# STM32lab.net
KiCad netlist of a schematic drawn in Altium Designer
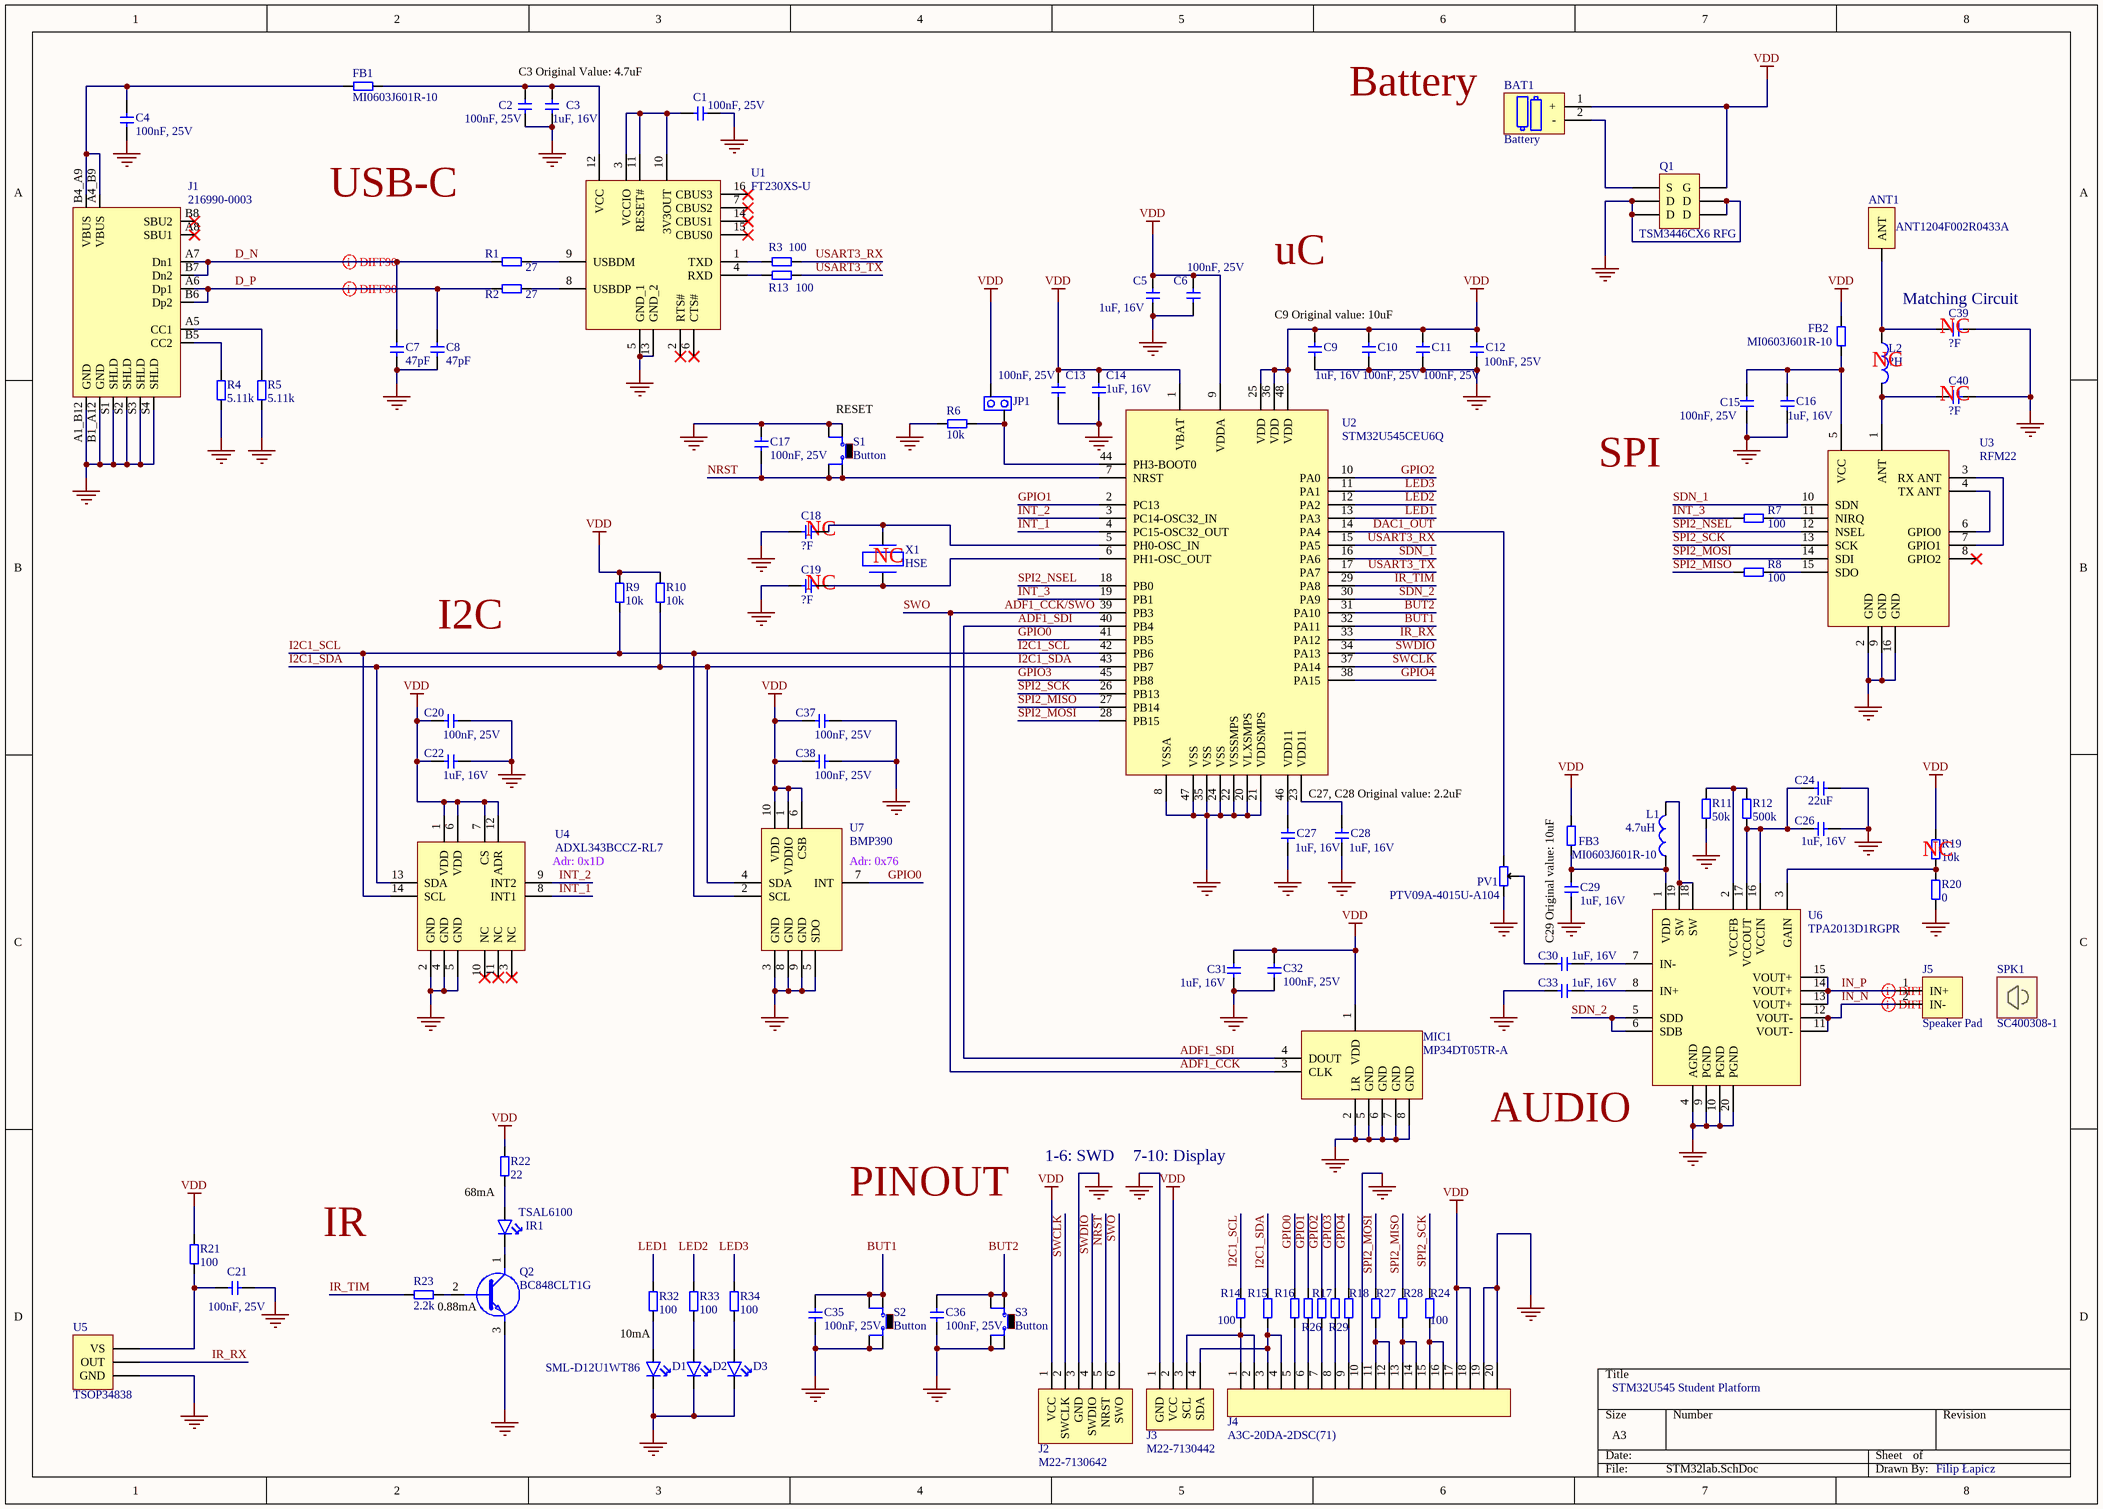
[diagram p0: STM32lab.SchDoc]

(export (version "E")
  (design (tool "Eeschema 10.0.6"))
  (components
    (comp (ref "ANT1")
      (value "ANT1204F002R0433A")
      (footprint "CHIP_R0433A_YAG")
      (description "Antennas 433MHz 50 Ohm 1W CHIP ANTENNA")
      (fields (field (name "MANUFACTURER") "Pulse"))
      (libsource (lib "Schlib") (part "ANT1204F002R0433A"))
    )
    (comp (ref "BAT1") (value "Battery") (footprint "2462") (libsource (lib "Schlib") (part "Battery")))
    (comp (ref "C1")
      (value "100nF, 25V")
      (footprint "CAPC1608X90N")
      (description "Multilayer Ceramic Capacitors MLCC - SMD/SMT 25V 0.1uF X5R 0603 10 %")
      (fields
        (field (name "MANUFACTURER") "Samsung")
        (field (name "MANUFACTURER PART NUMBER") "CL10B104JB8NNND")
      )
      (libsource (lib "Schlib") (part "TMK107BJ104KA-T"))
    )
    (comp (ref "C2")
      (value "100nF, 25V")
      (footprint "CAPC1608X90N")
      (description "Multilayer Ceramic Capacitors MLCC - SMD/SMT 25V 0.1uF X5R 0603 10 %")
      (fields
        (field (name "MANUFACTURER") "Samsung")
        (field (name "MANUFACTURER PART NUMBER") "CL10B104JB8NNND")
      )
      (libsource (lib "Schlib") (part "TMK107BJ104KA-T"))
    )
    (comp (ref "C3")
      (value "1uF, 16V")
      (footprint "CAPC1608X90N")
      (description "Multilayer Ceramic Capacitors (High dielectric type), 16V, 1 uF, ± 20 %, 0603, X5R, RoHS")
      (fields
        (field (name "MANUFACTURER") "Taiyo Yuden")
        (field (name "MANUFACTURER PART NUMBER") "EMK107BJ105MA-T")
      )
      (libsource (lib "Schlib") (part "EMK107BJ105MA-T"))
    )
    (comp (ref "C4")
      (value "100nF, 25V")
      (footprint "CAPC1608X90N")
      (description "Multilayer Ceramic Capacitors MLCC - SMD/SMT 25V 0.1uF X5R 0603 10 %")
      (fields
        (field (name "MANUFACTURER") "Samsung")
        (field (name "MANUFACTURER PART NUMBER") "CL10B104JB8NNND")
      )
      (libsource (lib "Schlib") (part "TMK107BJ104KA-T"))
    )
    (comp (ref "C5")
      (value "1uF, 16V")
      (footprint "CAPC1608X90N")
      (description "Multilayer Ceramic Capacitors (High dielectric type), 16V, 1 uF, ± 20 %, 0603, X5R, RoHS")
      (fields
        (field (name "MANUFACTURER") "Taiyo Yuden")
        (field (name "MANUFACTURER PART NUMBER") "EMK107BJ105MA-T")
      )
      (libsource (lib "Schlib") (part "EMK107BJ105MA-T"))
    )
    (comp (ref "C6")
      (value "100nF, 25V")
      (footprint "CAPC1608X90N")
      (description "Multilayer Ceramic Capacitors MLCC - SMD/SMT 25V 0.1uF X5R 0603 10 %")
      (fields
        (field (name "MANUFACTURER") "Samsung")
        (field (name "MANUFACTURER PART NUMBER") "CL10B104JB8NNND")
      )
      (libsource (lib "Schlib") (part "TMK107BJ104KA-T"))
    )
    (comp (ref "C7")
      (value "47pF")
      (footprint "CAPC1608X90N")
      (description "No model capacitor")
      (libsource (lib "Schlib") (part "Capacitor"))
    )
    (comp (ref "C8")
      (value "47pF")
      (footprint "CAPC1608X90N")
      (description "No model capacitor")
      (libsource (lib "Schlib") (part "Capacitor"))
    )
    (comp (ref "C9")
      (value "1uF, 16V")
      (footprint "CAPC1608X90N")
      (description "Multilayer Ceramic Capacitors (High dielectric type), 16V, 1 uF, ± 20 %, 0603, X5R, RoHS")
      (fields
        (field (name "MANUFACTURER") "Taiyo Yuden")
        (field (name "MANUFACTURER PART NUMBER") "EMK107BJ105MA-T")
      )
      (libsource (lib "Schlib") (part "EMK107BJ105MA-T"))
    )
    (comp (ref "C10")
      (value "100nF, 25V")
      (footprint "CAPC1608X90N")
      (description "Multilayer Ceramic Capacitors MLCC - SMD/SMT 25V 0.1uF X5R 0603 10 %")
      (fields
        (field (name "MANUFACTURER") "Samsung")
        (field (name "MANUFACTURER PART NUMBER") "CL10B104JB8NNND")
      )
      (libsource (lib "Schlib") (part "TMK107BJ104KA-T"))
    )
    (comp (ref "C11")
      (value "100nF, 25V")
      (footprint "CAPC1608X90N")
      (description "Multilayer Ceramic Capacitors MLCC - SMD/SMT 25V 0.1uF X5R 0603 10 %")
      (fields
        (field (name "MANUFACTURER") "Samsung")
        (field (name "MANUFACTURER PART NUMBER") "CL10B104JB8NNND")
      )
      (libsource (lib "Schlib") (part "TMK107BJ104KA-T"))
    )
    (comp (ref "C12")
      (value "100nF, 25V")
      (footprint "CAPC1608X90N")
      (description "Multilayer Ceramic Capacitors MLCC - SMD/SMT 25V 0.1uF X5R 0603 10 %")
      (fields
        (field (name "MANUFACTURER") "Samsung")
        (field (name "MANUFACTURER PART NUMBER") "CL10B104JB8NNND")
      )
      (libsource (lib "Schlib") (part "TMK107BJ104KA-T"))
    )
    (comp (ref "C13")
      (value "100nF, 25V")
      (footprint "CAPC1608X90N")
      (description "Multilayer Ceramic Capacitors MLCC - SMD/SMT 25V 0.1uF X5R 0603 10 %")
      (fields
        (field (name "MANUFACTURER") "Samsung")
        (field (name "MANUFACTURER PART NUMBER") "CL10B104JB8NNND")
      )
      (libsource (lib "Schlib") (part "TMK107BJ104KA-T"))
    )
    (comp (ref "C14")
      (value "1uF, 16V")
      (footprint "CAPC1608X90N")
      (description "Multilayer Ceramic Capacitors (High dielectric type), 16V, 1 uF, ± 20 %, 0603, X5R, RoHS")
      (fields
        (field (name "MANUFACTURER") "Taiyo Yuden")
        (field (name "MANUFACTURER PART NUMBER") "EMK107BJ105MA-T")
      )
      (libsource (lib "Schlib") (part "EMK107BJ105MA-T"))
    )
    (comp (ref "C15")
      (value "100nF, 25V")
      (footprint "CAPC1608X90N")
      (description "Multilayer Ceramic Capacitors MLCC - SMD/SMT 25V 0.1uF X5R 0603 10 %")
      (fields
        (field (name "MANUFACTURER") "Samsung")
        (field (name "MANUFACTURER PART NUMBER") "CL10B104JB8NNND")
      )
      (libsource (lib "Schlib") (part "TMK107BJ104KA-T"))
    )
    (comp (ref "C16")
      (value "1uF, 16V")
      (footprint "CAPC1608X90N")
      (description "Multilayer Ceramic Capacitors (High dielectric type), 16V, 1 uF, ± 20 %, 0603, X5R, RoHS")
      (fields
        (field (name "MANUFACTURER") "Taiyo Yuden")
        (field (name "MANUFACTURER PART NUMBER") "EMK107BJ105MA-T")
      )
      (libsource (lib "Schlib") (part "EMK107BJ105MA-T"))
    )
    (comp (ref "C17")
      (value "100nF, 25V")
      (footprint "CAPC1608X90N")
      (description "Multilayer Ceramic Capacitors MLCC - SMD/SMT 25V 0.1uF X5R 0603 10 %")
      (fields
        (field (name "MANUFACTURER") "Samsung")
        (field (name "MANUFACTURER PART NUMBER") "CL10B104JB8NNND")
      )
      (libsource (lib "Schlib") (part "TMK107BJ104KA-T"))
    )
    (comp (ref "C18")
      (value "?F")
      (footprint "CAPC1608X90N")
      (description "No model capacitor")
      (libsource (lib "Schlib") (part "Capacitor"))
    )
    (comp (ref "C19")
      (value "?F")
      (footprint "CAPC1608X90N")
      (description "No model capacitor")
      (libsource (lib "Schlib") (part "Capacitor"))
    )
    (comp (ref "C20")
      (value "100nF, 25V")
      (footprint "CAPC1608X90N")
      (description "Multilayer Ceramic Capacitors MLCC - SMD/SMT 25V 0.1uF X5R 0603 10 %")
      (fields
        (field (name "MANUFACTURER") "Samsung")
        (field (name "MANUFACTURER PART NUMBER") "CL10B104JB8NNND")
      )
      (libsource (lib "Schlib") (part "TMK107BJ104KA-T"))
    )
    (comp (ref "C21")
      (value "100nF, 25V")
      (footprint "CAPC1608X90N")
      (description "Multilayer Ceramic Capacitors MLCC - SMD/SMT 25V 0.1uF X5R 0603 10 %")
      (fields
        (field (name "MANUFACTURER") "Samsung")
        (field (name "MANUFACTURER PART NUMBER") "CL10B104JB8NNND")
      )
      (libsource (lib "Schlib") (part "TMK107BJ104KA-T"))
    )
    (comp (ref "C22")
      (value "1uF, 16V")
      (footprint "CAPC1608X90N")
      (description "Multilayer Ceramic Capacitors (High dielectric type), 16V, 1 uF, ± 20 %, 0603, X5R, RoHS")
      (fields
        (field (name "MANUFACTURER") "Taiyo Yuden")
        (field (name "MANUFACTURER PART NUMBER") "EMK107BJ105MA-T")
      )
      (libsource (lib "Schlib") (part "EMK107BJ105MA-T"))
    )
    (comp (ref "C24")
      (value "22uF")
      (footprint "CAPC1608X90N")
      (description "No model capacitor")
      (libsource (lib "Schlib") (part "Capacitor"))
    )
    (comp (ref "C26")
      (value "1uF, 16V")
      (footprint "CAPC1608X90N")
      (description "Multilayer Ceramic Capacitors (High dielectric type), 16V, 1 uF, ± 20 %, 0603, X5R, RoHS")
      (fields
        (field (name "MANUFACTURER") "Taiyo Yuden")
        (field (name "MANUFACTURER PART NUMBER") "EMK107BJ105MA-T")
      )
      (libsource (lib "Schlib") (part "EMK107BJ105MA-T"))
    )
    (comp (ref "C27")
      (value "1uF, 16V")
      (footprint "CAPC1608X90N")
      (description "Multilayer Ceramic Capacitors (High dielectric type), 16V, 1 uF, ± 20 %, 0603, X5R, RoHS")
      (fields
        (field (name "MANUFACTURER") "Taiyo Yuden")
        (field (name "MANUFACTURER PART NUMBER") "EMK107BJ105MA-T")
      )
      (libsource (lib "Schlib") (part "EMK107BJ105MA-T"))
    )
    (comp (ref "C28")
      (value "1uF, 16V")
      (footprint "CAPC1608X90N")
      (description "Multilayer Ceramic Capacitors (High dielectric type), 16V, 1 uF, ± 20 %, 0603, X5R, RoHS")
      (fields
        (field (name "MANUFACTURER") "Taiyo Yuden")
        (field (name "MANUFACTURER PART NUMBER") "EMK107BJ105MA-T")
      )
      (libsource (lib "Schlib") (part "EMK107BJ105MA-T"))
    )
    (comp (ref "C29")
      (value "1uF, 16V")
      (footprint "CAPC1608X90N")
      (description "Multilayer Ceramic Capacitors (High dielectric type), 16V, 1 uF, ± 20 %, 0603, X5R, RoHS")
      (fields
        (field (name "MANUFACTURER") "Taiyo Yuden")
        (field (name "MANUFACTURER PART NUMBER") "EMK107BJ105MA-T")
      )
      (libsource (lib "Schlib") (part "EMK107BJ105MA-T"))
    )
    (comp (ref "C30")
      (value "1uF, 16V")
      (footprint "CAPC1608X90N")
      (description "Multilayer Ceramic Capacitors (High dielectric type), 16V, 1 uF, ± 20 %, 0603, X5R, RoHS")
      (fields
        (field (name "MANUFACTURER") "Taiyo Yuden")
        (field (name "MANUFACTURER PART NUMBER") "EMK107BJ105MA-T")
      )
      (libsource (lib "Schlib") (part "EMK107BJ105MA-T"))
    )
    (comp (ref "C31")
      (value "1uF, 16V")
      (footprint "CAPC1608X90N")
      (description "Multilayer Ceramic Capacitors (High dielectric type), 16V, 1 uF, ± 20 %, 0603, X5R, RoHS")
      (fields
        (field (name "MANUFACTURER") "Taiyo Yuden")
        (field (name "MANUFACTURER PART NUMBER") "EMK107BJ105MA-T")
      )
      (libsource (lib "Schlib") (part "EMK107BJ105MA-T"))
    )
    (comp (ref "C32")
      (value "100nF, 25V")
      (footprint "CAPC1608X90N")
      (description "Multilayer Ceramic Capacitors MLCC - SMD/SMT 25V 0.1uF X5R 0603 10 %")
      (fields
        (field (name "MANUFACTURER") "Samsung")
        (field (name "MANUFACTURER PART NUMBER") "CL10B104JB8NNND")
      )
      (libsource (lib "Schlib") (part "TMK107BJ104KA-T"))
    )
    (comp (ref "C33")
      (value "1uF, 16V")
      (footprint "CAPC1608X90N")
      (description "Multilayer Ceramic Capacitors (High dielectric type), 16V, 1 uF, ± 20 %, 0603, X5R, RoHS")
      (fields
        (field (name "MANUFACTURER") "Taiyo Yuden")
        (field (name "MANUFACTURER PART NUMBER") "EMK107BJ105MA-T")
      )
      (libsource (lib "Schlib") (part "EMK107BJ105MA-T"))
    )
    (comp (ref "C35")
      (value "100nF, 25V")
      (footprint "CAPC1608X90N")
      (description "Multilayer Ceramic Capacitors MLCC - SMD/SMT 25V 0.1uF X5R 0603 10 %")
      (fields
        (field (name "MANUFACTURER") "Samsung")
        (field (name "MANUFACTURER PART NUMBER") "CL10B104JB8NNND")
      )
      (libsource (lib "Schlib") (part "TMK107BJ104KA-T"))
    )
    (comp (ref "C36")
      (value "100nF, 25V")
      (footprint "CAPC1608X90N")
      (description "Multilayer Ceramic Capacitors MLCC - SMD/SMT 25V 0.1uF X5R 0603 10 %")
      (fields
        (field (name "MANUFACTURER") "Samsung")
        (field (name "MANUFACTURER PART NUMBER") "CL10B104JB8NNND")
      )
      (libsource (lib "Schlib") (part "TMK107BJ104KA-T"))
    )
    (comp (ref "C37")
      (value "100nF, 25V")
      (footprint "CAPC1608X90N")
      (description "Multilayer Ceramic Capacitors MLCC - SMD/SMT 25V 0.1uF X5R 0603 10 %")
      (fields
        (field (name "MANUFACTURER") "Samsung")
        (field (name "MANUFACTURER PART NUMBER") "CL10B104JB8NNND")
      )
      (libsource (lib "Schlib") (part "TMK107BJ104KA-T"))
    )
    (comp (ref "C38")
      (value "100nF, 25V")
      (footprint "CAPC1608X90N")
      (description "Multilayer Ceramic Capacitors MLCC - SMD/SMT 25V 0.1uF X5R 0603 10 %")
      (fields
        (field (name "MANUFACTURER") "Samsung")
        (field (name "MANUFACTURER PART NUMBER") "CL10B104JB8NNND")
      )
      (libsource (lib "Schlib") (part "TMK107BJ104KA-T"))
    )
    (comp (ref "C39")
      (value "?F")
      (footprint "CAPC1608X90N")
      (description "No model capacitor")
      (libsource (lib "Schlib") (part "Capacitor"))
    )
    (comp (ref "C40")
      (value "?F")
      (footprint "CAPC1608X90N")
      (description "No model capacitor")
      (libsource (lib "Schlib") (part "Capacitor"))
    )
    (comp (ref "D1")
      (value "SML-D12U1WT86")
      (footprint "LEDC1608X65N")
      (description "Single Color LED, Red, Milky White, 1.2mm")
      (fields (field (name "MANUFACTURER") "Rohm"))
      (libsource (lib "Schlib") (part "SML-D12U1WT86"))
    )
    (comp (ref "D2")
      (value "SML-D12U1WT86")
      (footprint "LEDC1608X65N")
      (description "Single Color LED, Red, Milky White, 1.2mm")
      (fields (field (name "MANUFACTURER") "Rohm"))
      (libsource (lib "Schlib") (part "SML-D12U1WT86"))
    )
    (comp (ref "D3")
      (value "SML-D12U1WT86")
      (footprint "LEDC1608X65N")
      (description "Single Color LED, Red, Milky White, 1.2mm")
      (fields (field (name "MANUFACTURER") "Rohm"))
      (libsource (lib "Schlib") (part "SML-D12U1WT86"))
    )
    (comp (ref "FB1")
      (value "MI0603J601R-10")
      (footprint "RESC1608X55N")
      (description "Ferrite Chip, 1 Function(s), 1A, 2 Pin(s)")
      (fields (field (name "MANUFACTURER") "Laird"))
      (libsource (lib "Schlib") (part "MI0603J601R-10"))
    )
    (comp (ref "FB2")
      (value "MI0603J601R-10")
      (footprint "RESC1608X55N")
      (description "Ferrite Chip, 1 Function(s), 1A, 2 Pin(s)")
      (fields (field (name "MANUFACTURER") "Laird"))
      (libsource (lib "Schlib") (part "MI0603J601R-10"))
    )
    (comp (ref "FB3")
      (value "MI0603J601R-10")
      (footprint "RESC1608X55N")
      (description "Ferrite Chip, 1 Function(s), 1A, 2 Pin(s)")
      (fields (field (name "MANUFACTURER") "Laird"))
      (libsource (lib "Schlib") (part "MI0603J601R-10"))
    )
    (comp (ref "IR1")
      (value "TSAL6100")
      (footprint "TSAL")
      (description "λP=940nm VF=1.35V")
      (fields (field (name "MANUFACTURER") "Vishay"))
      (libsource (lib "Schlib") (part "TSAL6100"))
    )
    (comp (ref "J1")
      (value "216990-0003")
      (footprint "MOLEX_2169900003")
      (description "USB Type C - Connector, Mid-mount, SMT, CH0.58, 16pos ¦ Molex Incorporated 216990-0003")
      (fields (field (name "MANUFACTURER") "Molex"))
      (libsource (lib "Schlib") (part "216990-0003"))
    )
    (comp (ref "J2")
      (value "M22-7130642")
      (footprint "6-wire")
      (fields (field (name "MANUFACTURER") "Harwin"))
      (libsource (lib "Schlib") (part "M22-7130642"))
    )
    (comp (ref "J3")
      (value "M22-7130442")
      (footprint "4-wire")
      (fields (field (name "MANUFACTURER") "Harwin"))
      (libsource (lib "Schlib") (part "M22-7130442"))
    )
    (comp (ref "J4")
      (value "A3C-20DA-2DSC(71)")
      (footprint "20-wire")
      (description "Board Connector")
      (fields (field (name "MANUFACTURER") "Hirose"))
      (libsource (lib "Schlib") (part "A3C-20DA-2DSC(71)"))
    )
    (comp (ref "J5") (value "Speaker Pad") (footprint "Pad") (libsource (lib "Schlib") (part "Speaker Pad")))
    (comp (ref "JP1")
      (value "~")
      (footprint "10129378902002BLF")
      (description "Conn Unshrouded Header HDR 2 POS 2.54mm Solder ST Thru-Hole Poly Bag")
      (fields
        (field (name "MANUFACTURER") "Amphenol ICC / FCI")
        (field (name "MANUFACTURER PART NUMBER") "10129378-902002BLF")
      )
      (libsource (lib "Schlib") (part "10129378-902002BLF"))
    )
    (comp (ref "L1")
      (value "4.7uH")
      (footprint "RESC1608X55N")
      (fields
        (field (name "MOUSER PART NUMBER") "810-MLZ1608N4R7LTD25")
        (field (name "MANUFACTURER_PART_NUMBER") "MLZ1608N4R7LTD25")
      )
      (libsource (lib "Schlib") (part "MLZ1608N4R7LTD25"))
    )
    (comp (ref "L2")
      (value "?H")
      (footprint "RESC1608X55N")
      (fields
        (field (name "MOUSER PART NUMBER") "810-MLZ1608N4R7LTD25")
        (field (name "MANUFACTURER_PART_NUMBER") "MLZ1608N4R7LTD25")
      )
      (libsource (lib "Schlib") (part "MLZ1608N4R7LTD25"))
    )
    (comp (ref "MIC1")
      (value "MP34DT05TR-A")
      (footprint "MP34DT05TRA")
      (description "Consumer Circuit, CMOS, CBGA4")
      (fields (field (name "MANUFACTURER") "STMicroelectronics"))
      (libsource (lib "Schlib") (part "MP34DT05TR-A"))
    )
    (comp (ref "PV1")
      (value "PTV09A-4015U-A104")
      (footprint "PTV09A-4015U-A104")
      (description "Potentiometer, Carbon, 0.05W, 100000ohm, 20V, 20% +/-Tol, 1 Turn(s)")
      (fields (field (name "MANUFACTURER") "Bourns") (field (name "TOLERANCE") "20%"))
      (libsource (lib "Schlib") (part "PTV09A-4015U-A104"))
    )
    (comp (ref "Q1")
      (value "TSM3446CX6 RFG")
      (footprint "TRANS_TSM3446CX6_RFG")
      (description "20V, 5.3A, Single N-Channel Power MOSFET")
      (fields (field (name "MANUFACTURER") "Taiwan Semiconductor"))
      (libsource (lib "Schlib") (part "TSM3446CX6 RFG"))
    )
    (comp (ref "Q2")
      (value "BC848CLT1G")
      (footprint "SOT-23TO-236_318-08_ONS")
      (description "Small Signal Bipolar Transistor, 0.1A I(C), 30V V(BR)CEO, 1-Element, NPN, Silicon, TO-236")
      (fields (field (name "MANUFACTURER") "ON Semiconductor"))
      (libsource (lib "Schlib") (part "BC848CLT1G"))
    )
    (comp (ref "R1")
      (value "27")
      (footprint "RESC1608X55N")
      (description "No model resistor")
      (libsource (lib "Schlib") (part "Resistor"))
    )
    (comp (ref "R2")
      (value "27")
      (footprint "RESC1608X55N")
      (description "No model resistor")
      (libsource (lib "Schlib") (part "Resistor"))
    )
    (comp (ref "R3")
      (value "100")
      (footprint "RESC1608X55N")
      (description "No model resistor")
      (libsource (lib "Schlib") (part "Resistor"))
    )
    (comp (ref "R4")
      (value "5.11k")
      (footprint "RESC1608X55N")
      (description "No model resistor")
      (libsource (lib "Schlib") (part "Resistor"))
    )
    (comp (ref "R5")
      (value "5.11k")
      (footprint "RESC1608X55N")
      (description "No model resistor")
      (libsource (lib "Schlib") (part "Resistor"))
    )
    (comp (ref "R6")
      (value "10k")
      (footprint "RESC1608X55N")
      (description "Thick Film Resistors - SMD 10 kOhms 100 mW 0603 5%")
      (fields
        (field (name "MANUFACTURER") "Yageo")
        (field (name "MANUFACTURER PART NUMBER") "RC0603JR-0710KP")
      )
      (libsource (lib "Schlib") (part "RC0603JR-0710KP"))
    )
    (comp (ref "R7")
      (value "100")
      (footprint "RESC1608X55N")
      (description "No model resistor")
      (libsource (lib "Schlib") (part "Resistor"))
    )
    (comp (ref "R8")
      (value "100")
      (footprint "RESC1608X55N")
      (description "No model resistor")
      (libsource (lib "Schlib") (part "Resistor"))
    )
    (comp (ref "R9")
      (value "10k")
      (footprint "RESC1608X55N")
      (description "Thick Film Resistors - SMD 10 kOhms 100 mW 0603 5%")
      (fields
        (field (name "MANUFACTURER") "Yageo")
        (field (name "MANUFACTURER PART NUMBER") "RC0603JR-0710KP")
      )
      (libsource (lib "Schlib") (part "RC0603JR-0710KP"))
    )
    (comp (ref "R10")
      (value "10k")
      (footprint "RESC1608X55N")
      (description "Thick Film Resistors - SMD 10 kOhms 100 mW 0603 5%")
      (fields
        (field (name "MANUFACTURER") "Yageo")
        (field (name "MANUFACTURER PART NUMBER") "RC0603JR-0710KP")
      )
      (libsource (lib "Schlib") (part "RC0603JR-0710KP"))
    )
    (comp (ref "R11")
      (value "50k")
      (footprint "RESC1608X55N")
      (description "No model resistor")
      (libsource (lib "Schlib") (part "Resistor"))
    )
    (comp (ref "R12")
      (value "500k")
      (footprint "RESC1608X55N")
      (description "No model resistor")
      (libsource (lib "Schlib") (part "Resistor"))
    )
    (comp (ref "R13")
      (value "100")
      (footprint "RESC1608X55N")
      (description "No model resistor")
      (libsource (lib "Schlib") (part "Resistor"))
    )
    (comp (ref "R14")
      (value "100")
      (footprint "RESC1608X55N")
      (description "No model resistor")
      (libsource (lib "Schlib") (part "Resistor"))
    )
    (comp (ref "R15")
      (value "100")
      (footprint "RESC1608X55N")
      (description "No model resistor")
      (libsource (lib "Schlib") (part "Resistor"))
    )
    (comp (ref "R16")
      (value "100")
      (footprint "RESC1608X55N")
      (description "No model resistor")
      (libsource (lib "Schlib") (part "Resistor"))
    )
    (comp (ref "R17")
      (value "100")
      (footprint "RESC1608X55N")
      (description "No model resistor")
      (libsource (lib "Schlib") (part "Resistor"))
    )
    (comp (ref "R18")
      (value "100")
      (footprint "RESC1608X55N")
      (description "No model resistor")
      (libsource (lib "Schlib") (part "Resistor"))
    )
    (comp (ref "R19")
      (value "10k")
      (footprint "RESC1608X55N")
      (description "No model resistor")
      (libsource (lib "Schlib") (part "Resistor"))
    )
    (comp (ref "R20")
      (value "0")
      (footprint "RESC1608X55N")
      (description "No model resistor")
      (libsource (lib "Schlib") (part "Resistor"))
    )
    (comp (ref "R21")
      (value "100")
      (footprint "RESC1608X55N")
      (description "No model resistor")
      (libsource (lib "Schlib") (part "Resistor"))
    )
    (comp (ref "R22")
      (value "22")
      (footprint "RESC1608X55N")
      (description "No model resistor")
      (libsource (lib "Schlib") (part "Resistor"))
    )
    (comp (ref "R23")
      (value "2.2k")
      (footprint "RESC1608X55N")
      (description "No model resistor")
      (libsource (lib "Schlib") (part "Resistor"))
    )
    (comp (ref "R24")
      (value "100")
      (footprint "RESC1608X55N")
      (description "No model resistor")
      (libsource (lib "Schlib") (part "Resistor"))
    )
    (comp (ref "R26")
      (value "100")
      (footprint "RESC1608X55N")
      (description "No model resistor")
      (libsource (lib "Schlib") (part "Resistor"))
    )
    (comp (ref "R27")
      (value "100")
      (footprint "RESC1608X55N")
      (description "No model resistor")
      (libsource (lib "Schlib") (part "Resistor"))
    )
    (comp (ref "R28")
      (value "100")
      (footprint "RESC1608X55N")
      (description "No model resistor")
      (libsource (lib "Schlib") (part "Resistor"))
    )
    (comp (ref "R29")
      (value "100")
      (footprint "RESC1608X55N")
      (description "No model resistor")
      (libsource (lib "Schlib") (part "Resistor"))
    )
    (comp (ref "R32")
      (value "100")
      (footprint "RESC1608X55N")
      (description "No model resistor")
      (libsource (lib "Schlib") (part "Resistor"))
    )
    (comp (ref "R33")
      (value "100")
      (footprint "RESC1608X55N")
      (description "No model resistor")
      (libsource (lib "Schlib") (part "Resistor"))
    )
    (comp (ref "R34")
      (value "100")
      (footprint "RESC1608X55N")
      (description "No model resistor")
      (libsource (lib "Schlib") (part "Resistor"))
    )
    (comp (ref "S1")
      (value "Button")
      (footprint "TS026650BK260SCRD")
      (description "Switch Tactile OFF (ON) SPST Round Button PC Pins 0.05A 12VDC 60000Cycles 2.6N Thru-Hole Bag")
      (fields
        (field (name "MANUFACTURER") "CUI Devices")
        (field (name "MANUFACTURER PART NUMBER") "TS02-66-50-BK-260-SCR-D")
      )
      (libsource (lib "Schlib") (part "TS02-66-50-BK-260-SCR-D"))
    )
    (comp (ref "S2")
      (value "Button")
      (footprint "TS026650BK260SCRD")
      (description "Switch Tactile OFF (ON) SPST Round Button PC Pins 0.05A 12VDC 60000Cycles 2.6N Thru-Hole Bag")
      (fields
        (field (name "MANUFACTURER") "CUI Devices")
        (field (name "MANUFACTURER PART NUMBER") "TS02-66-50-BK-260-SCR-D")
      )
      (libsource (lib "Schlib") (part "TS02-66-50-BK-260-SCR-D"))
    )
    (comp (ref "S3")
      (value "Button")
      (footprint "TS026650BK260SCRD")
      (description "Switch Tactile OFF (ON) SPST Round Button PC Pins 0.05A 12VDC 60000Cycles 2.6N Thru-Hole Bag")
      (fields
        (field (name "MANUFACTURER") "CUI Devices")
        (field (name "MANUFACTURER PART NUMBER") "TS02-66-50-BK-260-SCR-D")
      )
      (libsource (lib "Schlib") (part "TS02-66-50-BK-260-SCR-D"))
    )
    (comp (ref "SPK1")
      (value "SC400308-1")
      (footprint "SC400308")
      (description "SC Series 2 W 8 O 20 kHz Rectangular Frame Mount Dynamic Speaker")
      (fields (field (name "MANUFACTURER") "DB Unlimited"))
      (libsource (lib "Schlib") (part "SC400308-1"))
    )
    (comp (ref "U1")
      (value "FT230XS-U")
      (footprint "SOP64P599X175-16N")
      (description "USB Interface IC USB to Basic Serial UART IC SSOP-16")
      (fields (field (name "MOUSER PART NUMBER") "895-FT230XS-U"))
      (libsource (lib "Schlib") (part "FT230XS-U"))
    )
    (comp (ref "U2")
      (value "STM32U545CEU6Q")
      (footprint "UFQFPN-48_STM")
      (description "MCU 32-bit ARM Cortex M33 RISC 512KB Flash 1.8V/2.5V/3.3V 48-Pin UFQFPN EP Tray")
      (fields (field (name "MANUFACTURER") "STMicroelectronics"))
      (libsource (lib "Schlib") (part "STM32U545CEU6Q"))
    )
    (comp (ref "U3")
      (value "RFM22")
      (footprint "RFM22B-S2_HRF")
      (description "ISM transceiver module 1.8-3.6V 240-930MHz +17dBm")
      (libsource (lib "Schlib") (part "RFM22"))
    )
    (comp (ref "U4")
      (value "ADXL343BCCZ-RL7")
      (footprint "PQFN80P300X500X100-14N")
      (description "Accelerometer Triple ±2/±4/±8/±16g 2V to 3.6V 14-Pin LGA T/R")
      (fields (field (name "MANUFACTURER") "Analog Devices"))
      (libsource (lib "Schlib") (part "ADXL343BCCZ-RL7"))
    )
    (comp (ref "U5")
      (value "TSOP34838")
      (footprint "TO_TSOP31236_VIS")
      (description "Logic Output Photo IC")
      (fields (field (name "MANUFACTURER") "Vishay"))
      (libsource (lib "Schlib") (part "TSOP34838"))
    )
    (comp (ref "U6")
      (value "TPA2013D1RGPR")
      (footprint "QFN50P400X400X100-21N-D")
      (description "Audio Amplifier, 2.7W, 2 Channel(s), 1 Func, PQCC20")
      (fields (field (name "MANUFACTURER") "Texas Instruments"))
      (libsource (lib "Schlib") (part "TPA2013D1RGPR"))
    )
    (comp (ref "U7")
      (value "BMP390")
      (footprint "10LGA_2X2X0p75_BOS")
      (description "Board Mount Pressure Sensor 300hPa to 1250hPa Barometric 10-Pin LGA Module T/R")
      (fields (field (name "MANUFACTURER") "Bosch Tools"))
      (libsource (lib "Schlib") (part "BMP390"))
    )
    (comp (ref "X1")
      (value "HSE")
      (footprint "HC49USMFF5F1873728MHZ")
      (libsource (lib "Schlib") (part "HSE"))
    )
  )
  (nets
    (net (code "1") (name "/ADF1_CCK") (class "Default")
      (node (ref "J2") (pin "6") (pinfunction "SWO_6") (pintype "passive"))
      (node (ref "MIC1") (pin "3") (pinfunction "CLK_3") (pintype "passive"))
      (node (ref "U2") (pin "39") (pinfunction "PB3_39") (pintype "passive"))
    )
    (net (code "2") (name "/ADF1_SDI") (class "Default")
      (node (ref "MIC1") (pin "4") (pinfunction "DOUT_4") (pintype "passive"))
      (node (ref "U2") (pin "40") (pinfunction "PB4_40") (pintype "passive"))
    )
    (net (code "3") (name "/BUT1") (class "Default")
      (node (ref "C35") (pin "2") (pinfunction "2_2") (pintype "passive"))
      (node (ref "S2") (pin "1") (pinfunction "1_1") (pintype "passive"))
      (node (ref "S2") (pin "2") (pinfunction "2_2") (pintype "passive"))
      (node (ref "U2") (pin "32") (pinfunction "PA11_32") (pintype "passive"))
    )
    (net (code "4") (name "/BUT2") (class "Default")
      (node (ref "C36") (pin "2") (pinfunction "2_2") (pintype "passive"))
      (node (ref "S3") (pin "1") (pinfunction "1_1") (pintype "passive"))
      (node (ref "S3") (pin "2") (pinfunction "2_2") (pintype "passive"))
      (node (ref "U2") (pin "31") (pinfunction "PA10_31") (pintype "passive"))
    )
    (net (code "5") (name "/DAC1_OUT") (class "Default")
      (node (ref "PV1") (pin "1") (pinfunction "1_1") (pintype "passive"))
      (node (ref "U2") (pin "14") (pinfunction "PA4_14") (pintype "passive"))
    )
    (net (code "6") (name "/D_N") (class "Default")
      (node (ref "C7") (pin "2") (pinfunction "2_2") (pintype "passive"))
      (node (ref "J1") (pin "A7") (pinfunction "Dn1_A7") (pintype "passive"))
      (node (ref "J1") (pin "B7") (pinfunction "Dn2_B7") (pintype "passive"))
      (node (ref "R1") (pin "1") (pinfunction "1_1") (pintype "passive"))
    )
    (net (code "7") (name "/D_P") (class "Default")
      (node (ref "C8") (pin "2") (pinfunction "2_2") (pintype "passive"))
      (node (ref "J1") (pin "A6") (pinfunction "Dp1_A6") (pintype "passive"))
      (node (ref "J1") (pin "B6") (pinfunction "Dp2_B6") (pintype "passive"))
      (node (ref "R2") (pin "1") (pinfunction "1_1") (pintype "passive"))
    )
    (net (code "8") (name "/GPIO0") (class "Default")
      (node (ref "R16") (pin "1") (pinfunction "1_1") (pintype "passive"))
      (node (ref "U2") (pin "41") (pinfunction "PB5_41") (pintype "passive"))
      (node (ref "U7") (pin "7") (pinfunction "INT_7") (pintype "passive"))
    )
    (net (code "9") (name "/GPIO1") (class "Default")
      (node (ref "R26") (pin "1") (pinfunction "1_1") (pintype "passive"))
      (node (ref "U2") (pin "2") (pinfunction "PC13_2") (pintype "passive"))
    )
    (net (code "10") (name "/GPIO2") (class "Default")
      (node (ref "R17") (pin "1") (pinfunction "1_1") (pintype "passive"))
      (node (ref "U2") (pin "10") (pinfunction "PA0_10") (pintype "passive"))
    )
    (net (code "11") (name "/GPIO3") (class "Default")
      (node (ref "R29") (pin "1") (pinfunction "1_1") (pintype "passive"))
      (node (ref "U2") (pin "45") (pinfunction "PB8_45") (pintype "passive"))
    )
    (net (code "12") (name "/GPIO4") (class "Default")
      (node (ref "R18") (pin "1") (pinfunction "1_1") (pintype "passive"))
      (node (ref "U2") (pin "38") (pinfunction "PA15_38") (pintype "passive"))
    )
    (net (code "13") (name "/I2C1_SCL") (class "Default")
      (node (ref "R14") (pin "1") (pinfunction "1_1") (pintype "passive"))
      (node (ref "R9") (pin "1") (pinfunction "1_1") (pintype "passive"))
      (node (ref "U2") (pin "42") (pinfunction "PB6_42") (pintype "passive"))
      (node (ref "U4") (pin "14") (pinfunction "SCL_14") (pintype "passive"))
      (node (ref "U7") (pin "2") (pinfunction "SCL_2") (pintype "passive"))
    )
    (net (code "14") (name "/I2C1_SDA") (class "Default")
      (node (ref "R10") (pin "1") (pinfunction "1_1") (pintype "passive"))
      (node (ref "R15") (pin "1") (pinfunction "1_1") (pintype "passive"))
      (node (ref "U2") (pin "43") (pinfunction "PB7_43") (pintype "passive"))
      (node (ref "U4") (pin "13") (pinfunction "SDA_13") (pintype "passive"))
      (node (ref "U7") (pin "4") (pinfunction "SDA_4") (pintype "passive"))
    )
    (net (code "15") (name "/INT_1") (class "Default")
      (node (ref "U2") (pin "4") (pinfunction "PC15-OSC32_OUT_4") (pintype "passive"))
      (node (ref "U4") (pin "8") (pinfunction "INT1_8") (pintype "passive"))
    )
    (net (code "16") (name "/INT_2") (class "Default")
      (node (ref "U2") (pin "3") (pinfunction "PC14-OSC32_IN_3") (pintype "passive"))
      (node (ref "U4") (pin "9") (pinfunction "INT2_9") (pintype "passive"))
    )
    (net (code "17") (name "/INT_3") (class "Default")
      (node (ref "R7") (pin "1") (pinfunction "1_1") (pintype "passive"))
      (node (ref "U2") (pin "19") (pinfunction "PB1_19") (pintype "passive"))
    )
    (net (code "18") (name "/IN_N") (class "Default")
      (node (ref "J5") (pin "2") (pinfunction "IN-_2") (pintype "passive"))
      (node (ref "U6") (pin "11") (pinfunction "VOUT-_11") (pintype "passive"))
      (node (ref "U6") (pin "12") (pinfunction "VOUT-_12") (pintype "passive"))
    )
    (net (code "19") (name "/IN_P") (class "Default")
      (node (ref "J5") (pin "1") (pinfunction "IN+_1") (pintype "passive"))
      (node (ref "U6") (pin "13") (pinfunction "VOUT+_13") (pintype "passive"))
      (node (ref "U6") (pin "14") (pinfunction "VOUT+_14") (pintype "passive"))
      (node (ref "U6") (pin "15") (pinfunction "VOUT+_15") (pintype "passive"))
    )
    (net (code "20") (name "/IR_RX") (class "Default")
      (node (ref "U2") (pin "33") (pinfunction "PA12_33") (pintype "passive"))
      (node (ref "U5") (pin "1") (pinfunction "OUT_1") (pintype "passive"))
    )
    (net (code "21") (name "/IR_TIM") (class "Default")
      (node (ref "R23") (pin "1") (pinfunction "1_1") (pintype "passive"))
      (node (ref "U2") (pin "29") (pinfunction "PA8_29") (pintype "passive"))
    )
    (net (code "22") (name "/LED1") (class "Default")
      (node (ref "R32") (pin "2") (pinfunction "2_2") (pintype "passive"))
      (node (ref "U2") (pin "13") (pinfunction "PA3_13") (pintype "passive"))
    )
    (net (code "23") (name "/LED2") (class "Default")
      (node (ref "R33") (pin "2") (pinfunction "2_2") (pintype "passive"))
      (node (ref "U2") (pin "12") (pinfunction "PA2_12") (pintype "passive"))
    )
    (net (code "24") (name "/LED3") (class "Default")
      (node (ref "R34") (pin "2") (pinfunction "2_2") (pintype "passive"))
      (node (ref "U2") (pin "11") (pinfunction "PA1_11") (pintype "passive"))
    )
    (net (code "25") (name "/NRST") (class "Default")
      (node (ref "C17") (pin "1") (pinfunction "1_1") (pintype "passive"))
      (node (ref "J2") (pin "5") (pinfunction "NRST_5") (pintype "passive"))
      (node (ref "S1") (pin "3") (pinfunction "3_3") (pintype "passive"))
      (node (ref "S1") (pin "4") (pinfunction "4_4") (pintype "passive"))
      (node (ref "U2") (pin "7") (pinfunction "NRST_7") (pintype "passive"))
    )
    (net (code "26") (name "/SDN_1") (class "Default")
      (node (ref "U2") (pin "16") (pinfunction "PA6_16") (pintype "passive"))
      (node (ref "U3") (pin "10") (pinfunction "SDN_10") (pintype "passive"))
    )
    (net (code "27") (name "/SDN_2") (class "Default")
      (node (ref "U2") (pin "30") (pinfunction "PA9_30") (pintype "passive"))
      (node (ref "U6") (pin "5") (pinfunction "SDD_5") (pintype "passive"))
      (node (ref "U6") (pin "6") (pinfunction "SDB_6") (pintype "passive"))
    )
    (net (code "28") (name "/SPI2_MISO") (class "Default")
      (node (ref "R28") (pin "1") (pinfunction "1_1") (pintype "passive"))
      (node (ref "R8") (pin "1") (pinfunction "1_1") (pintype "passive"))
      (node (ref "U2") (pin "27") (pinfunction "PB14_27") (pintype "passive"))
    )
    (net (code "29") (name "/SPI2_MOSI") (class "Default")
      (node (ref "R27") (pin "1") (pinfunction "1_1") (pintype "passive"))
      (node (ref "U2") (pin "28") (pinfunction "PB15_28") (pintype "passive"))
      (node (ref "U3") (pin "14") (pinfunction "SDI_14") (pintype "passive"))
    )
    (net (code "30") (name "/SPI2_NSEL") (class "Default")
      (node (ref "U2") (pin "18") (pinfunction "PB0_18") (pintype "passive"))
      (node (ref "U3") (pin "12") (pinfunction "NSEL_12") (pintype "passive"))
    )
    (net (code "31") (name "/SPI2_SCK") (class "Default")
      (node (ref "R24") (pin "1") (pinfunction "1_1") (pintype "passive"))
      (node (ref "U2") (pin "26") (pinfunction "PB13_26") (pintype "passive"))
      (node (ref "U3") (pin "13") (pinfunction "SCK_13") (pintype "passive"))
    )
    (net (code "32") (name "/SWCLK") (class "Default")
      (node (ref "J2") (pin "2") (pinfunction "SWCLK_2") (pintype "passive"))
      (node (ref "U2") (pin "37") (pinfunction "PA14_37") (pintype "passive"))
    )
    (net (code "33") (name "/SWDIO") (class "Default")
      (node (ref "J2") (pin "4") (pinfunction "SWDIO_4") (pintype "passive"))
      (node (ref "U2") (pin "34") (pinfunction "PA13_34") (pintype "passive"))
    )
    (net (code "34") (name "/USART3_RX") (class "Default")
      (node (ref "R3") (pin "2") (pinfunction "2_2") (pintype "passive"))
      (node (ref "U2") (pin "15") (pinfunction "PA5_15") (pintype "passive"))
    )
    (net (code "35") (name "/USART3_TX") (class "Default")
      (node (ref "R13") (pin "2") (pinfunction "2_2") (pintype "passive"))
      (node (ref "U2") (pin "17") (pinfunction "PA7_17") (pintype "passive"))
    )
    (net (code "36") (name "GND") (class "Default")
      (node (ref "C1") (pin "1") (pinfunction "1_1") (pintype "passive"))
      (node (ref "C10") (pin "1") (pinfunction "1_1") (pintype "passive"))
      (node (ref "C11") (pin "1") (pinfunction "1_1") (pintype "passive"))
      (node (ref "C12") (pin "1") (pinfunction "1_1") (pintype "passive"))
      (node (ref "C13") (pin "1") (pinfunction "1_1") (pintype "passive"))
      (node (ref "C14") (pin "1") (pinfunction "1_1") (pintype "passive"))
      (node (ref "C15") (pin "1") (pinfunction "1_1") (pintype "passive"))
      (node (ref "C16") (pin "1") (pinfunction "1_1") (pintype "passive"))
      (node (ref "C17") (pin "2") (pinfunction "2_2") (pintype "passive"))
      (node (ref "C18") (pin "1") (pinfunction "1_1") (pintype "passive"))
      (node (ref "C19") (pin "1") (pinfunction "1_1") (pintype "passive"))
      (node (ref "C2") (pin "1") (pinfunction "1_1") (pintype "passive"))
      (node (ref "C20") (pin "2") (pinfunction "2_2") (pintype "passive"))
      (node (ref "C21") (pin "1") (pinfunction "1_1") (pintype "passive"))
      (node (ref "C22") (pin "2") (pinfunction "2_2") (pintype "passive"))
      (node (ref "C24") (pin "2") (pinfunction "2_2") (pintype "passive"))
      (node (ref "C26") (pin "1") (pinfunction "1_1") (pintype "passive"))
      (node (ref "C27") (pin "1") (pinfunction "1_1") (pintype "passive"))
      (node (ref "C28") (pin "1") (pinfunction "1_1") (pintype "passive"))
      (node (ref "C29") (pin "2") (pinfunction "2_2") (pintype "passive"))
      (node (ref "C3") (pin "1") (pinfunction "1_1") (pintype "passive"))
      (node (ref "C31") (pin "1") (pinfunction "1_1") (pintype "passive"))
      (node (ref "C32") (pin "1") (pinfunction "1_1") (pintype "passive"))
      (node (ref "C33") (pin "1") (pinfunction "1_1") (pintype "passive"))
      (node (ref "C35") (pin "1") (pinfunction "1_1") (pintype "passive"))
      (node (ref "C36") (pin "1") (pinfunction "1_1") (pintype "passive"))
      (node (ref "C37") (pin "1") (pinfunction "1_1") (pintype "passive"))
      (node (ref "C38") (pin "1") (pinfunction "1_1") (pintype "passive"))
      (node (ref "C39") (pin "2") (pinfunction "2_2") (pintype "passive"))
      (node (ref "C4") (pin "1") (pinfunction "1_1") (pintype "passive"))
      (node (ref "C40") (pin "2") (pinfunction "2_2") (pintype "passive"))
      (node (ref "C5") (pin "1") (pinfunction "1_1") (pintype "passive"))
      (node (ref "C6") (pin "1") (pinfunction "1_1") (pintype "passive"))
      (node (ref "C7") (pin "1") (pinfunction "1_1") (pintype "passive"))
      (node (ref "C8") (pin "1") (pinfunction "1_1") (pintype "passive"))
      (node (ref "C9") (pin "1") (pinfunction "1_1") (pintype "passive"))
      (node (ref "D1") (pin "2") (pinfunction "4_2") (pintype "passive"))
      (node (ref "D2") (pin "2") (pinfunction "4_2") (pintype "passive"))
      (node (ref "D3") (pin "2") (pinfunction "4_2") (pintype "passive"))
      (node (ref "J1") (pin "A1_B12") (pinfunction "GND_A1_B12") (pintype "passive"))
      (node (ref "J1") (pin "B1_A12") (pinfunction "GND_B1_A12") (pintype "passive"))
      (node (ref "J1") (pin "S1") (pinfunction "SHLD_S1") (pintype "passive"))
      (node (ref "J1") (pin "S2") (pinfunction "SHLD_S2") (pintype "passive"))
      (node (ref "J1") (pin "S3") (pinfunction "SHLD_S3") (pintype "passive"))
      (node (ref "J1") (pin "S4") (pinfunction "SHLD_S4") (pintype "passive"))
      (node (ref "J2") (pin "3") (pinfunction "GND_3") (pintype "passive"))
      (node (ref "J3") (pin "1") (pinfunction "GND_1") (pintype "passive"))
      (node (ref "J4") (pin "10") (pintype "passive"))
      (node (ref "J4") (pin "19") (pintype "passive"))
      (node (ref "J4") (pin "20") (pintype "passive"))
      (node (ref "MIC1") (pin "2") (pinfunction "LR_2") (pintype "passive"))
      (node (ref "MIC1") (pin "5") (pinfunction "GND_5") (pintype "passive"))
      (node (ref "MIC1") (pin "6") (pinfunction "GND_6") (pintype "passive"))
      (node (ref "MIC1") (pin "7") (pinfunction "GND_7") (pintype "passive"))
      (node (ref "MIC1") (pin "8") (pinfunction "GND_8") (pintype "passive"))
      (node (ref "PV1") (pin "3") (pinfunction "3_3") (pintype "passive"))
      (node (ref "Q1") (pin "2") (pinfunction "D_2") (pintype "passive"))
      (node (ref "Q1") (pin "3") (pinfunction "D_3") (pintype "passive"))
      (node (ref "Q1") (pin "5") (pinfunction "D_5") (pintype "passive"))
      (node (ref "Q1") (pin "6") (pinfunction "D_6") (pintype "passive"))
      (node (ref "Q2") (pin "3") (pinfunction "E_3") (pintype "passive"))
      (node (ref "R11") (pin "1") (pinfunction "1_1") (pintype "passive"))
      (node (ref "R20") (pin "1") (pinfunction "1_1") (pintype "passive"))
      (node (ref "R4") (pin "1") (pinfunction "1_1") (pintype "passive"))
      (node (ref "R5") (pin "1") (pinfunction "1_1") (pintype "passive"))
      (node (ref "R6") (pin "2") (pinfunction "2_2") (pintype "passive"))
      (node (ref "S1") (pin "1") (pinfunction "1_1") (pintype "passive"))
      (node (ref "S1") (pin "2") (pinfunction "2_2") (pintype "passive"))
      (node (ref "S2") (pin "3") (pinfunction "3_3") (pintype "passive"))
      (node (ref "S2") (pin "4") (pinfunction "4_4") (pintype "passive"))
      (node (ref "S3") (pin "3") (pinfunction "3_3") (pintype "passive"))
      (node (ref "S3") (pin "4") (pinfunction "4_4") (pintype "passive"))
      (node (ref "U1") (pin "13") (pinfunction "GND_2_13") (pintype "passive"))
      (node (ref "U1") (pin "5") (pinfunction "GND_1_5") (pintype "passive"))
      (node (ref "U2") (pin "20") (pinfunction "VLXSMPS_20") (pintype "passive"))
      (node (ref "U2") (pin "21") (pinfunction "VDDSMPS_21") (pintype "passive"))
      (node (ref "U2") (pin "22") (pinfunction "VSSSMPS_22") (pintype "passive"))
      (node (ref "U2") (pin "24") (pinfunction "VSS_24") (pintype "passive"))
      (node (ref "U2") (pin "35") (pinfunction "VSS_35") (pintype "passive"))
      (node (ref "U2") (pin "47") (pinfunction "VSS_47") (pintype "passive"))
      (node (ref "U2") (pin "8") (pinfunction "VSSA_8") (pintype "passive"))
      (node (ref "U3") (pin "16") (pinfunction "GND_16") (pintype "passive"))
      (node (ref "U3") (pin "2") (pinfunction "GND_2") (pintype "passive"))
      (node (ref "U3") (pin "9") (pinfunction "GND_9") (pintype "passive"))
      (node (ref "U4") (pin "2") (pinfunction "GND_2") (pintype "passive"))
      (node (ref "U4") (pin "4") (pinfunction "GND_4") (pintype "passive"))
      (node (ref "U4") (pin "5") (pinfunction "GND_5") (pintype "passive"))
      (node (ref "U5") (pin "2") (pinfunction "GND_2") (pintype "passive"))
      (node (ref "U6") (pin "10") (pinfunction "PGND_10") (pintype "passive"))
      (node (ref "U6") (pin "20") (pinfunction "PGND_20") (pintype "passive"))
      (node (ref "U6") (pin "4") (pinfunction "AGND_4") (pintype "passive"))
      (node (ref "U6") (pin "9") (pinfunction "PGND_9") (pintype "passive"))
      (node (ref "U7") (pin "3") (pinfunction "GND_3") (pintype "passive"))
      (node (ref "U7") (pin "5") (pinfunction "SDO_5") (pintype "passive"))
      (node (ref "U7") (pin "8") (pinfunction "GND_8") (pintype "passive"))
      (node (ref "U7") (pin "9") (pinfunction "GND_9") (pintype "passive"))
    )
    (net (code "37") (name "Net-(ANT1-ANT)") (class "Default")
      (node (ref "ANT1") (pin "1") (pinfunction "ANT_1") (pintype "passive"))
      (node (ref "C39") (pin "1") (pinfunction "1_1") (pintype "passive"))
      (node (ref "L2") (pin "1") (pinfunction "1_1") (pintype "passive"))
    )
    (net (code "38") (name "Net-(BAT1--)") (class "Default")
      (node (ref "BAT1") (pin "2") (pinfunction "-_2") (pintype "passive"))
      (node (ref "Q1") (pin "1") (pinfunction "S_1") (pintype "passive"))
    )
    (net (code "39") (name "Net-(C4-Pad2)") (class "Default")
      (node (ref "C4") (pin "2") (pinfunction "2_2") (pintype "passive"))
      (node (ref "FB1") (pin "1") (pinfunction "1_1") (pintype "passive"))
      (node (ref "J1") (pin "A4_B9") (pinfunction "VBUS_A4_B9") (pintype "passive"))
      (node (ref "J1") (pin "B4_A9") (pinfunction "VBUS_B4_A9") (pintype "passive"))
    )
    (net (code "40") (name "Net-(C27-Pad2)") (class "Default")
      (node (ref "C27") (pin "2") (pinfunction "2_2") (pintype "passive"))
      (node (ref "U2") (pin "46") (pinfunction "VDD11_46") (pintype "passive"))
    )
    (net (code "41") (name "Net-(C28-Pad2)") (class "Default")
      (node (ref "C28") (pin "2") (pinfunction "2_2") (pintype "passive"))
      (node (ref "U2") (pin "23") (pinfunction "VDD11_23") (pintype "passive"))
    )
    (net (code "42") (name "Net-(C30-Pad1)") (class "Default")
      (node (ref "C30") (pin "1") (pinfunction "1_1") (pintype "passive"))
      (node (ref "PV1") (pin "2") (pinfunction "2_2") (pintype "passive"))
    )
    (net (code "43") (name "Net-(D1-3)") (class "Default")
      (node (ref "D1") (pin "1") (pinfunction "3_1") (pintype "passive"))
      (node (ref "R32") (pin "1") (pinfunction "1_1") (pintype "passive"))
    )
    (net (code "44") (name "Net-(D2-3)") (class "Default")
      (node (ref "D2") (pin "1") (pinfunction "3_1") (pintype "passive"))
      (node (ref "R33") (pin "1") (pinfunction "1_1") (pintype "passive"))
    )
    (net (code "45") (name "Net-(D3-3)") (class "Default")
      (node (ref "D3") (pin "1") (pinfunction "3_1") (pintype "passive"))
      (node (ref "R34") (pin "1") (pinfunction "1_1") (pintype "passive"))
    )
    (net (code "46") (name "Net-(IR1-3)") (class "Default")
      (node (ref "IR1") (pin "1") (pinfunction "3_1") (pintype "passive"))
      (node (ref "R22") (pin "1") (pinfunction "1_1") (pintype "passive"))
    )
    (net (code "47") (name "Net-(IR1-4)") (class "Default")
      (node (ref "IR1") (pin "2") (pinfunction "4_2") (pintype "passive"))
      (node (ref "Q2") (pin "1") (pinfunction "C_1") (pintype "passive"))
    )
    (net (code "48") (name "Net-(J1-CC1)") (class "Default")
      (node (ref "J1") (pin "A5") (pinfunction "CC1_A5") (pintype "passive"))
      (node (ref "R5") (pin "2") (pinfunction "2_2") (pintype "passive"))
    )
    (net (code "49") (name "Net-(J1-CC2)") (class "Default")
      (node (ref "J1") (pin "B5") (pinfunction "CC2_B5") (pintype "passive"))
      (node (ref "R4") (pin "2") (pinfunction "2_2") (pintype "passive"))
    )
    (net (code "50") (name "Net-(J3-SCL)") (class "Default")
      (node (ref "J3") (pin "3") (pinfunction "SCL_3") (pintype "passive"))
      (node (ref "J4") (pin "1") (pintype "passive"))
      (node (ref "J4") (pin "2") (pintype "passive"))
      (node (ref "R14") (pin "2") (pinfunction "2_2") (pintype "passive"))
    )
    (net (code "51") (name "Net-(J3-SDA)") (class "Default")
      (node (ref "J3") (pin "4") (pinfunction "SDA_4") (pintype "passive"))
      (node (ref "J4") (pin "3") (pintype "passive"))
      (node (ref "J4") (pin "4") (pintype "passive"))
      (node (ref "R15") (pin "2") (pinfunction "2_2") (pintype "passive"))
    )
    (net (code "52") (name "Net-(J4-Pad5)") (class "Default")
      (node (ref "J4") (pin "5") (pintype "passive"))
      (node (ref "R16") (pin "2") (pinfunction "2_2") (pintype "passive"))
    )
    (net (code "53") (name "Net-(J4-Pad6)") (class "Default")
      (node (ref "J4") (pin "6") (pintype "passive"))
      (node (ref "R26") (pin "2") (pinfunction "2_2") (pintype "passive"))
    )
    (net (code "54") (name "Net-(J4-Pad7)") (class "Default")
      (node (ref "J4") (pin "7") (pintype "passive"))
      (node (ref "R17") (pin "2") (pinfunction "2_2") (pintype "passive"))
    )
    (net (code "55") (name "Net-(J4-Pad8)") (class "Default")
      (node (ref "J4") (pin "8") (pintype "passive"))
      (node (ref "R29") (pin "2") (pinfunction "2_2") (pintype "passive"))
    )
    (net (code "56") (name "Net-(J4-Pad9)") (class "Default")
      (node (ref "J4") (pin "9") (pintype "passive"))
      (node (ref "R18") (pin "2") (pinfunction "2_2") (pintype "passive"))
    )
    (net (code "57") (name "Net-(J4-Pad11)") (class "Default")
      (node (ref "J4") (pin "11") (pintype "passive"))
      (node (ref "J4") (pin "12") (pintype "passive"))
      (node (ref "R27") (pin "2") (pinfunction "2_2") (pintype "passive"))
    )
    (net (code "58") (name "Net-(J4-Pad13)") (class "Default")
      (node (ref "J4") (pin "13") (pintype "passive"))
      (node (ref "J4") (pin "14") (pintype "passive"))
      (node (ref "R28") (pin "2") (pinfunction "2_2") (pintype "passive"))
    )
    (net (code "59") (name "Net-(J4-Pad15)") (class "Default")
      (node (ref "J4") (pin "15") (pintype "passive"))
      (node (ref "J4") (pin "16") (pintype "passive"))
      (node (ref "R24") (pin "2") (pinfunction "2_2") (pintype "passive"))
    )
    (net (code "60") (name "Net-(JP1-17)") (class "Default")
      (node (ref "JP1") (pin "2") (pinfunction "17_2") (pintype "passive"))
      (node (ref "R6") (pin "1") (pinfunction "1_1") (pintype "passive"))
      (node (ref "U2") (pin "44") (pinfunction "PH3-BOOT0_44") (pintype "passive"))
    )
    (net (code "61") (name "Net-(L1-Pad2)") (class "Default")
      (node (ref "L1") (pin "2") (pinfunction "2_2") (pintype "passive"))
      (node (ref "U6") (pin "18") (pinfunction "SW_18") (pintype "passive"))
      (node (ref "U6") (pin "19") (pinfunction "SW_19") (pintype "passive"))
    )
    (net (code "62") (name "Net-(Q2-B)") (class "Default")
      (node (ref "Q2") (pin "2") (pinfunction "B_2") (pintype "passive"))
      (node (ref "R23") (pin "2") (pinfunction "2_2") (pintype "passive"))
    )
    (net (code "63") (name "Net-(U1-3V3OUT)") (class "Default")
      (node (ref "C1") (pin "2") (pinfunction "2_2") (pintype "passive"))
      (node (ref "U1") (pin "10") (pinfunction "3V3OUT_10") (pintype "passive"))
      (node (ref "U1") (pin "11") (pinfunction "RESET#_11") (pintype "passive"))
      (node (ref "U1") (pin "3") (pinfunction "VCCIO_3") (pintype "passive"))
    )
    (net (code "64") (name "Net-(U1-RXD)") (class "Default")
      (node (ref "R13") (pin "1") (pinfunction "1_1") (pintype "passive"))
      (node (ref "U1") (pin "4") (pinfunction "RXD_4") (pintype "passive"))
    )
    (net (code "65") (name "Net-(U1-TXD)") (class "Default")
      (node (ref "R3") (pin "1") (pinfunction "1_1") (pintype "passive"))
      (node (ref "U1") (pin "1") (pinfunction "TXD_1") (pintype "passive"))
    )
    (net (code "66") (name "Net-(U1-USBDM)") (class "Default")
      (node (ref "R1") (pin "2") (pinfunction "2_2") (pintype "passive"))
      (node (ref "U1") (pin "9") (pinfunction "USBDM_9") (pintype "passive"))
    )
    (net (code "67") (name "Net-(U1-USBDP)") (class "Default")
      (node (ref "R2") (pin "2") (pinfunction "2_2") (pintype "passive"))
      (node (ref "U1") (pin "8") (pinfunction "USBDP_8") (pintype "passive"))
    )
    (net (code "68") (name "Net-(U1-VCC)") (class "Default")
      (node (ref "C2") (pin "2") (pinfunction "2_2") (pintype "passive"))
      (node (ref "C3") (pin "2") (pinfunction "2_2") (pintype "passive"))
      (node (ref "FB1") (pin "2") (pinfunction "2_2") (pintype "passive"))
      (node (ref "U1") (pin "12") (pinfunction "VCC_12") (pintype "passive"))
    )
    (net (code "69") (name "Net-(U2-PH0-OSC_IN)") (class "Default")
      (node (ref "C18") (pin "2") (pinfunction "2_2") (pintype "passive"))
      (node (ref "U2") (pin "5") (pinfunction "PH0-OSC_IN_5") (pintype "passive"))
      (node (ref "X1") (pin "1") (pinfunction "1_1") (pintype "passive"))
    )
    (net (code "70") (name "Net-(U2-PH1-OSC_OUT)") (class "Default")
      (node (ref "C19") (pin "2") (pinfunction "2_2") (pintype "passive"))
      (node (ref "U2") (pin "6") (pinfunction "PH1-OSC_OUT_6") (pintype "passive"))
      (node (ref "X1") (pin "2") (pinfunction "2_2") (pintype "passive"))
    )
    (net (code "71") (name "Net-(U3-ANT)") (class "Default")
      (node (ref "C40") (pin "1") (pinfunction "1_1") (pintype "passive"))
      (node (ref "L2") (pin "2") (pinfunction "2_2") (pintype "passive"))
      (node (ref "U3") (pin "1") (pinfunction "ANT_1") (pintype "passive"))
    )
    (net (code "72") (name "Net-(U3-GPIO0)") (class "Default")
      (node (ref "U3") (pin "4") (pinfunction "TX_ANT_4") (pintype "passive"))
      (node (ref "U3") (pin "6") (pinfunction "GPIO0_6") (pintype "passive"))
    )
    (net (code "73") (name "Net-(U3-GPIO1)") (class "Default")
      (node (ref "U3") (pin "3") (pinfunction "RX_ANT_3") (pintype "passive"))
      (node (ref "U3") (pin "7") (pinfunction "GPIO1_7") (pintype "passive"))
    )
    (net (code "74") (name "Net-(U3-NIRQ)") (class "Default")
      (node (ref "R7") (pin "2") (pinfunction "2_2") (pintype "passive"))
      (node (ref "U3") (pin "11") (pinfunction "NIRQ_11") (pintype "passive"))
    )
    (net (code "75") (name "Net-(U3-SDO)") (class "Default")
      (node (ref "R8") (pin "2") (pinfunction "2_2") (pintype "passive"))
      (node (ref "U3") (pin "15") (pinfunction "SDO_15") (pintype "passive"))
    )
    (net (code "76") (name "Net-(U3-VCC)") (class "Default")
      (node (ref "C15") (pin "2") (pinfunction "2_2") (pintype "passive"))
      (node (ref "C16") (pin "2") (pinfunction "2_2") (pintype "passive"))
      (node (ref "FB2") (pin "1") (pinfunction "1_1") (pintype "passive"))
      (node (ref "U3") (pin "5") (pinfunction "VCC_5") (pintype "passive"))
    )
    (net (code "77") (name "Net-(U5-VS)") (class "Default")
      (node (ref "C21") (pin "2") (pinfunction "2_2") (pintype "passive"))
      (node (ref "R21") (pin "1") (pinfunction "1_1") (pintype "passive"))
      (node (ref "U5") (pin "3") (pinfunction "VS_3") (pintype "passive"))
    )
    (net (code "78") (name "Net-(U6-GAIN)") (class "Default")
      (node (ref "R19") (pin "1") (pinfunction "1_1") (pintype "passive"))
      (node (ref "R20") (pin "2") (pinfunction "2_2") (pintype "passive"))
      (node (ref "U6") (pin "3") (pinfunction "GAIN_3") (pintype "passive"))
    )
    (net (code "79") (name "Net-(U6-IN+)") (class "Default")
      (node (ref "C33") (pin "2") (pinfunction "2_2") (pintype "passive"))
      (node (ref "U6") (pin "8") (pinfunction "IN+_8") (pintype "passive"))
    )
    (net (code "80") (name "Net-(U6-IN-)") (class "Default")
      (node (ref "C30") (pin "2") (pinfunction "2_2") (pintype "passive"))
      (node (ref "U6") (pin "7") (pinfunction "IN-_7") (pintype "passive"))
    )
    (net (code "81") (name "Net-(U6-VCCFB)") (class "Default")
      (node (ref "R11") (pin "2") (pinfunction "2_2") (pintype "passive"))
      (node (ref "R12") (pin "2") (pinfunction "2_2") (pintype "passive"))
      (node (ref "U6") (pin "2") (pinfunction "VCCFB_2") (pintype "passive"))
    )
    (net (code "82") (name "Net-(U6-VCCIN)") (class "Default")
      (node (ref "C24") (pin "1") (pinfunction "1_1") (pintype "passive"))
      (node (ref "C26") (pin "2") (pinfunction "2_2") (pintype "passive"))
      (node (ref "R12") (pin "1") (pinfunction "1_1") (pintype "passive"))
      (node (ref "U6") (pin "16") (pinfunction "VCCIN_16") (pintype "passive"))
      (node (ref "U6") (pin "17") (pinfunction "VCCOUT_17") (pintype "passive"))
    )
    (net (code "83") (name "Net-(U6-VDD)") (class "Default")
      (node (ref "C29") (pin "1") (pinfunction "1_1") (pintype "passive"))
      (node (ref "FB3") (pin "1") (pinfunction "1_1") (pintype "passive"))
      (node (ref "L1") (pin "1") (pinfunction "1_1") (pintype "passive"))
      (node (ref "U6") (pin "1") (pinfunction "VDD_1") (pintype "passive"))
    )
    (net (code "84") (name "VDD") (class "Default")
      (node (ref "BAT1") (pin "1") (pinfunction "+_1") (pintype "passive"))
      (node (ref "C10") (pin "2") (pinfunction "2_2") (pintype "passive"))
      (node (ref "C11") (pin "2") (pinfunction "2_2") (pintype "passive"))
      (node (ref "C12") (pin "2") (pinfunction "2_2") (pintype "passive"))
      (node (ref "C13") (pin "2") (pinfunction "2_2") (pintype "passive"))
      (node (ref "C14") (pin "2") (pinfunction "2_2") (pintype "passive"))
      (node (ref "C20") (pin "1") (pinfunction "1_1") (pintype "passive"))
      (node (ref "C22") (pin "1") (pinfunction "1_1") (pintype "passive"))
      (node (ref "C31") (pin "2") (pinfunction "2_2") (pintype "passive"))
      (node (ref "C32") (pin "2") (pinfunction "2_2") (pintype "passive"))
      (node (ref "C37") (pin "2") (pinfunction "2_2") (pintype "passive"))
      (node (ref "C38") (pin "2") (pinfunction "2_2") (pintype "passive"))
      (node (ref "C5") (pin "2") (pinfunction "2_2") (pintype "passive"))
      (node (ref "C6") (pin "2") (pinfunction "2_2") (pintype "passive"))
      (node (ref "C9") (pin "2") (pinfunction "2_2") (pintype "passive"))
      (node (ref "FB2") (pin "2") (pinfunction "2_2") (pintype "passive"))
      (node (ref "FB3") (pin "2") (pinfunction "2_2") (pintype "passive"))
      (node (ref "J2") (pin "1") (pinfunction "VCC_1") (pintype "passive"))
      (node (ref "J3") (pin "2") (pinfunction "VCC_2") (pintype "passive"))
      (node (ref "J4") (pin "17") (pintype "passive"))
      (node (ref "J4") (pin "18") (pintype "passive"))
      (node (ref "JP1") (pin "1") (pinfunction "16_1") (pintype "passive"))
      (node (ref "MIC1") (pin "1") (pinfunction "VDD_1") (pintype "passive"))
      (node (ref "Q1") (pin "4") (pinfunction "G_4") (pintype "passive"))
      (node (ref "R10") (pin "2") (pinfunction "2_2") (pintype "passive"))
      (node (ref "R19") (pin "2") (pinfunction "2_2") (pintype "passive"))
      (node (ref "R21") (pin "2") (pinfunction "2_2") (pintype "passive"))
      (node (ref "R22") (pin "2") (pinfunction "2_2") (pintype "passive"))
      (node (ref "R9") (pin "2") (pinfunction "2_2") (pintype "passive"))
      (node (ref "U2") (pin "1") (pinfunction "VBAT_1") (pintype "passive"))
      (node (ref "U2") (pin "25") (pinfunction "VDD_25") (pintype "passive"))
      (node (ref "U2") (pin "36") (pinfunction "VDD_36") (pintype "passive"))
      (node (ref "U2") (pin "48") (pinfunction "VDD_48") (pintype "passive"))
      (node (ref "U2") (pin "9") (pinfunction "VDDA_9") (pintype "passive"))
      (node (ref "U4") (pin "1") (pinfunction "VDD_1") (pintype "passive"))
      (node (ref "U4") (pin "12") (pinfunction "ADR_12") (pintype "passive"))
      (node (ref "U4") (pin "6") (pinfunction "VDD_6") (pintype "passive"))
      (node (ref "U4") (pin "7") (pinfunction "CS_7") (pintype "passive"))
      (node (ref "U7") (pin "1") (pinfunction "VDDIO_1") (pintype "passive"))
      (node (ref "U7") (pin "10") (pinfunction "VDD_10") (pintype "passive"))
      (node (ref "U7") (pin "6") (pinfunction "CSB_6") (pintype "passive"))
    )
    (net (code "85") (name "unconnected-(J1-SBU1-PadA8)") (class "Default")
      (node (ref "J1") (pin "A8") (pinfunction "SBU1_A8") (pintype "passive+no_connect"))
    )
    (net (code "86") (name "unconnected-(J1-SBU2-PadB8)") (class "Default")
      (node (ref "J1") (pin "B8") (pinfunction "SBU2_B8") (pintype "passive+no_connect"))
    )
    (net (code "87") (name "unconnected-(U1-CBUS0-Pad15)") (class "Default")
      (node (ref "U1") (pin "15") (pinfunction "CBUS0_15") (pintype "passive+no_connect"))
    )
    (net (code "88") (name "unconnected-(U1-CBUS1-Pad14)") (class "Default")
      (node (ref "U1") (pin "14") (pinfunction "CBUS1_14") (pintype "passive+no_connect"))
    )
    (net (code "89") (name "unconnected-(U1-CBUS2-Pad7)") (class "Default")
      (node (ref "U1") (pin "7") (pinfunction "CBUS2_7") (pintype "passive+no_connect"))
    )
    (net (code "90") (name "unconnected-(U1-CBUS3-Pad16)") (class "Default")
      (node (ref "U1") (pin "16") (pinfunction "CBUS3_16") (pintype "passive+no_connect"))
    )
    (net (code "91") (name "unconnected-(U1-CTS#-Pad6)") (class "Default")
      (node (ref "U1") (pin "6") (pinfunction "CTS#_6") (pintype "passive+no_connect"))
    )
    (net (code "92") (name "unconnected-(U1-RTS#-Pad2)") (class "Default")
      (node (ref "U1") (pin "2") (pinfunction "RTS#_2") (pintype "passive+no_connect"))
    )
    (net (code "93") (name "unconnected-(U3-GPIO2-Pad8)") (class "Default")
      (node (ref "U3") (pin "8") (pinfunction "GPIO2_8") (pintype "passive+no_connect"))
    )
    (net (code "94") (name "unconnected-(U4-NC-Pad3)") (class "Default")
      (node (ref "U4") (pin "3") (pinfunction "NC_3") (pintype "passive+no_connect"))
    )
    (net (code "95") (name "unconnected-(U4-NC-Pad10)") (class "Default")
      (node (ref "U4") (pin "10") (pinfunction "NC_10") (pintype "passive+no_connect"))
    )
    (net (code "96") (name "unconnected-(U4-NC-Pad11)") (class "Default")
      (node (ref "U4") (pin "11") (pinfunction "NC_11") (pintype "passive+no_connect"))
    )
  )
)
